# FMC_HPC_TO_LPC_BREAKOUT_ROW_HPC1.net
KiCad netlist of a schematic drawn in Altium Designer
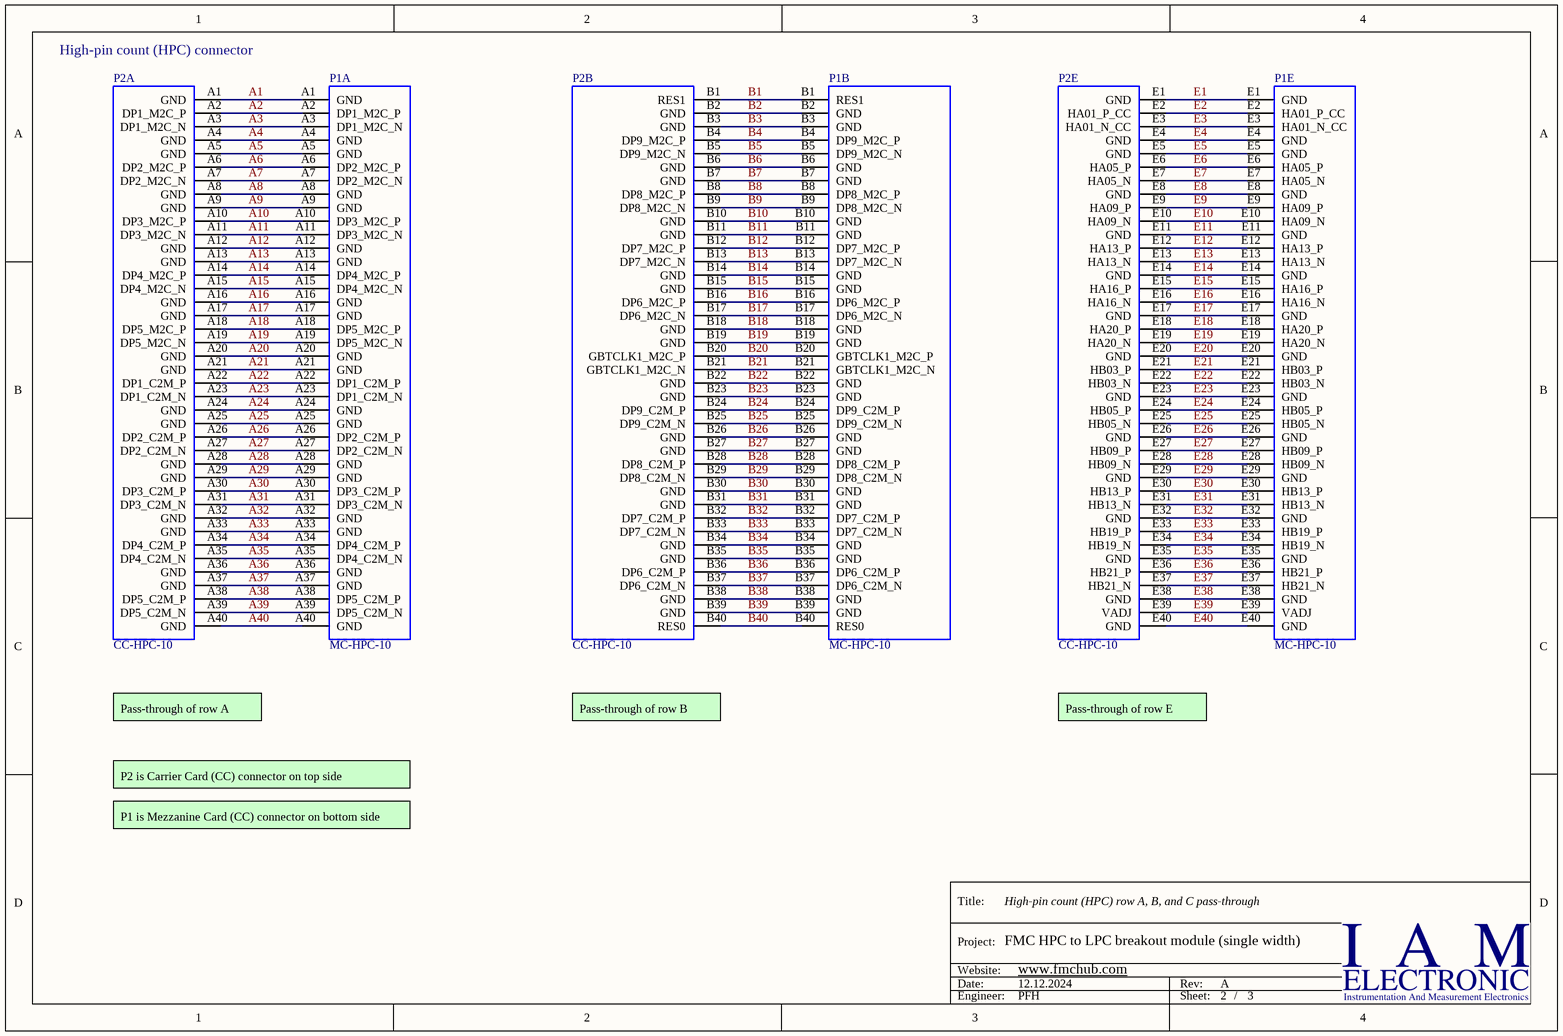
[diagram p0: FMC_HPC_TO_LPC_BREAKOUT_ROW_HPC1.SchDoc]

(export (version "E")
  (design (tool "Eeschema 10.0.6"))
  (components
    (comp (ref "P1")
      (value "MC-HPC-10")
      (footprint "ASP-134488-01")
      (description "MC-HPC-10, FMC High-pin count connector, lead free, 400 I/Os, male, 10 mm mated stack height")
      (fields (field (name "MANUFACTURER") "Samtec") (field (name "PART") "ASP-134488-01"))
      (libsource (lib "VITA_57_FMC") (part "MC-HPC-10"))
    )
    (comp (ref "P2")
      (value "CC-HPC-10")
      (footprint "ASP-134486-01")
      (description "CC-HPC-10, FMC High-pin count connector, lead free, 400 I/Os, female, 10 mm mated stack height")
      (fields (field (name "MANUFACTURER") "Samtec") (field (name "PART") "ASP-134486-01"))
      (libsource (lib "VITA_57_FMC") (part "CC-HPC-10"))
    )
  )
  (nets
    (net (code "1") (name "/A1") (class "Default")
      (node (ref "P1") (pin "A1") (pinfunction "GND_A1") (pintype "passive"))
      (node (ref "P2") (pin "A1") (pinfunction "GND_A1") (pintype "passive"))
    )
    (net (code "2") (name "/A2") (class "Default")
      (node (ref "P1") (pin "A2") (pinfunction "DP1_M2C_P_A2") (pintype "passive"))
      (node (ref "P2") (pin "A2") (pinfunction "DP1_M2C_P_A2") (pintype "passive"))
    )
    (net (code "3") (name "/A3") (class "Default")
      (node (ref "P1") (pin "A3") (pinfunction "DP1_M2C_N_A3") (pintype "passive"))
      (node (ref "P2") (pin "A3") (pinfunction "DP1_M2C_N_A3") (pintype "passive"))
    )
    (net (code "4") (name "/A4") (class "Default")
      (node (ref "P1") (pin "A4") (pinfunction "GND_A4") (pintype "passive"))
      (node (ref "P2") (pin "A4") (pinfunction "GND_A4") (pintype "passive"))
    )
    (net (code "5") (name "/A5") (class "Default")
      (node (ref "P1") (pin "A5") (pinfunction "GND_A5") (pintype "passive"))
      (node (ref "P2") (pin "A5") (pinfunction "GND_A5") (pintype "passive"))
    )
    (net (code "6") (name "/A6") (class "Default")
      (node (ref "P1") (pin "A6") (pinfunction "DP2_M2C_P_A6") (pintype "passive"))
      (node (ref "P2") (pin "A6") (pinfunction "DP2_M2C_P_A6") (pintype "passive"))
    )
    (net (code "7") (name "/A7") (class "Default")
      (node (ref "P1") (pin "A7") (pinfunction "DP2_M2C_N_A7") (pintype "passive"))
      (node (ref "P2") (pin "A7") (pinfunction "DP2_M2C_N_A7") (pintype "passive"))
    )
    (net (code "8") (name "/A8") (class "Default")
      (node (ref "P1") (pin "A8") (pinfunction "GND_A8") (pintype "passive"))
      (node (ref "P2") (pin "A8") (pinfunction "GND_A8") (pintype "passive"))
    )
    (net (code "9") (name "/A9") (class "Default")
      (node (ref "P1") (pin "A9") (pinfunction "GND_A9") (pintype "passive"))
      (node (ref "P2") (pin "A9") (pinfunction "GND_A9") (pintype "passive"))
    )
    (net (code "10") (name "/A10") (class "Default")
      (node (ref "P1") (pin "A10") (pinfunction "DP3_M2C_P_A10") (pintype "passive"))
      (node (ref "P2") (pin "A10") (pinfunction "DP3_M2C_P_A10") (pintype "passive"))
    )
    (net (code "11") (name "/A11") (class "Default")
      (node (ref "P1") (pin "A11") (pinfunction "DP3_M2C_N_A11") (pintype "passive"))
      (node (ref "P2") (pin "A11") (pinfunction "DP3_M2C_N_A11") (pintype "passive"))
    )
    (net (code "12") (name "/A12") (class "Default")
      (node (ref "P1") (pin "A12") (pinfunction "GND_A12") (pintype "passive"))
      (node (ref "P2") (pin "A12") (pinfunction "GND_A12") (pintype "passive"))
    )
    (net (code "13") (name "/A13") (class "Default")
      (node (ref "P1") (pin "A13") (pinfunction "GND_A13") (pintype "passive"))
      (node (ref "P2") (pin "A13") (pinfunction "GND_A13") (pintype "passive"))
    )
    (net (code "14") (name "/A14") (class "Default")
      (node (ref "P1") (pin "A14") (pinfunction "DP4_M2C_P_A14") (pintype "passive"))
      (node (ref "P2") (pin "A14") (pinfunction "DP4_M2C_P_A14") (pintype "passive"))
    )
    (net (code "15") (name "/A15") (class "Default")
      (node (ref "P1") (pin "A15") (pinfunction "DP4_M2C_N_A15") (pintype "passive"))
      (node (ref "P2") (pin "A15") (pinfunction "DP4_M2C_N_A15") (pintype "passive"))
    )
    (net (code "16") (name "/A16") (class "Default")
      (node (ref "P1") (pin "A16") (pinfunction "GND_A16") (pintype "passive"))
      (node (ref "P2") (pin "A16") (pinfunction "GND_A16") (pintype "passive"))
    )
    (net (code "17") (name "/A17") (class "Default")
      (node (ref "P1") (pin "A17") (pinfunction "GND_A17") (pintype "passive"))
      (node (ref "P2") (pin "A17") (pinfunction "GND_A17") (pintype "passive"))
    )
    (net (code "18") (name "/A18") (class "Default")
      (node (ref "P1") (pin "A18") (pinfunction "DP5_M2C_P_A18") (pintype "passive"))
      (node (ref "P2") (pin "A18") (pinfunction "DP5_M2C_P_A18") (pintype "passive"))
    )
    (net (code "19") (name "/A19") (class "Default")
      (node (ref "P1") (pin "A19") (pinfunction "DP5_M2C_N_A19") (pintype "passive"))
      (node (ref "P2") (pin "A19") (pinfunction "DP5_M2C_N_A19") (pintype "passive"))
    )
    (net (code "20") (name "/A20") (class "Default")
      (node (ref "P1") (pin "A20") (pinfunction "GND_A20") (pintype "passive"))
      (node (ref "P2") (pin "A20") (pinfunction "GND_A20") (pintype "passive"))
    )
    (net (code "21") (name "/A21") (class "Default")
      (node (ref "P1") (pin "A21") (pinfunction "GND_A21") (pintype "passive"))
      (node (ref "P2") (pin "A21") (pinfunction "GND_A21") (pintype "passive"))
    )
    (net (code "22") (name "/A22") (class "Default")
      (node (ref "P1") (pin "A22") (pinfunction "DP1_C2M_P_A22") (pintype "passive"))
      (node (ref "P2") (pin "A22") (pinfunction "DP1_C2M_P_A22") (pintype "passive"))
    )
    (net (code "23") (name "/A23") (class "Default")
      (node (ref "P1") (pin "A23") (pinfunction "DP1_C2M_N_A23") (pintype "passive"))
      (node (ref "P2") (pin "A23") (pinfunction "DP1_C2M_N_A23") (pintype "passive"))
    )
    (net (code "24") (name "/A24") (class "Default")
      (node (ref "P1") (pin "A24") (pinfunction "GND_A24") (pintype "passive"))
      (node (ref "P2") (pin "A24") (pinfunction "GND_A24") (pintype "passive"))
    )
    (net (code "25") (name "/A25") (class "Default")
      (node (ref "P1") (pin "A25") (pinfunction "GND_A25") (pintype "passive"))
      (node (ref "P2") (pin "A25") (pinfunction "GND_A25") (pintype "passive"))
    )
    (net (code "26") (name "/A26") (class "Default")
      (node (ref "P1") (pin "A26") (pinfunction "DP2_C2M_P_A26") (pintype "passive"))
      (node (ref "P2") (pin "A26") (pinfunction "DP2_C2M_P_A26") (pintype "passive"))
    )
    (net (code "27") (name "/A27") (class "Default")
      (node (ref "P1") (pin "A27") (pinfunction "DP2_C2M_N_A27") (pintype "passive"))
      (node (ref "P2") (pin "A27") (pinfunction "DP2_C2M_N_A27") (pintype "passive"))
    )
    (net (code "28") (name "/A28") (class "Default")
      (node (ref "P1") (pin "A28") (pinfunction "GND_A28") (pintype "passive"))
      (node (ref "P2") (pin "A28") (pinfunction "GND_A28") (pintype "passive"))
    )
    (net (code "29") (name "/A29") (class "Default")
      (node (ref "P1") (pin "A29") (pinfunction "GND_A29") (pintype "passive"))
      (node (ref "P2") (pin "A29") (pinfunction "GND_A29") (pintype "passive"))
    )
    (net (code "30") (name "/A30") (class "Default")
      (node (ref "P1") (pin "A30") (pinfunction "DP3_C2M_P_A30") (pintype "passive"))
      (node (ref "P2") (pin "A30") (pinfunction "DP3_C2M_P_A30") (pintype "passive"))
    )
    (net (code "31") (name "/A31") (class "Default")
      (node (ref "P1") (pin "A31") (pinfunction "DP3_C2M_N_A31") (pintype "passive"))
      (node (ref "P2") (pin "A31") (pinfunction "DP3_C2M_N_A31") (pintype "passive"))
    )
    (net (code "32") (name "/A32") (class "Default")
      (node (ref "P1") (pin "A32") (pinfunction "GND_A32") (pintype "passive"))
      (node (ref "P2") (pin "A32") (pinfunction "GND_A32") (pintype "passive"))
    )
    (net (code "33") (name "/A33") (class "Default")
      (node (ref "P1") (pin "A33") (pinfunction "GND_A33") (pintype "passive"))
      (node (ref "P2") (pin "A33") (pinfunction "GND_A33") (pintype "passive"))
    )
    (net (code "34") (name "/A34") (class "Default")
      (node (ref "P1") (pin "A34") (pinfunction "DP4_C2M_P_A34") (pintype "passive"))
      (node (ref "P2") (pin "A34") (pinfunction "DP4_C2M_P_A34") (pintype "passive"))
    )
    (net (code "35") (name "/A35") (class "Default")
      (node (ref "P1") (pin "A35") (pinfunction "DP4_C2M_N_A35") (pintype "passive"))
      (node (ref "P2") (pin "A35") (pinfunction "DP4_C2M_N_A35") (pintype "passive"))
    )
    (net (code "36") (name "/A36") (class "Default")
      (node (ref "P1") (pin "A36") (pinfunction "GND_A36") (pintype "passive"))
      (node (ref "P2") (pin "A36") (pinfunction "GND_A36") (pintype "passive"))
    )
    (net (code "37") (name "/A37") (class "Default")
      (node (ref "P1") (pin "A37") (pinfunction "GND_A37") (pintype "passive"))
      (node (ref "P2") (pin "A37") (pinfunction "GND_A37") (pintype "passive"))
    )
    (net (code "38") (name "/A38") (class "Default")
      (node (ref "P1") (pin "A38") (pinfunction "DP5_C2M_P_A38") (pintype "passive"))
      (node (ref "P2") (pin "A38") (pinfunction "DP5_C2M_P_A38") (pintype "passive"))
    )
    (net (code "39") (name "/A39") (class "Default")
      (node (ref "P1") (pin "A39") (pinfunction "DP5_C2M_N_A39") (pintype "passive"))
      (node (ref "P2") (pin "A39") (pinfunction "DP5_C2M_N_A39") (pintype "passive"))
    )
    (net (code "40") (name "/A40") (class "Default")
      (node (ref "P1") (pin "A40") (pinfunction "GND_A40") (pintype "passive"))
      (node (ref "P2") (pin "A40") (pinfunction "GND_A40") (pintype "passive"))
    )
    (net (code "41") (name "/B1") (class "Default")
      (node (ref "P1") (pin "B1") (pinfunction "RES1_B1") (pintype "passive"))
      (node (ref "P2") (pin "B1") (pinfunction "RES1_B1") (pintype "passive"))
    )
    (net (code "42") (name "/B2") (class "Default")
      (node (ref "P1") (pin "B2") (pinfunction "GND_B2") (pintype "passive"))
      (node (ref "P2") (pin "B2") (pinfunction "GND_B2") (pintype "passive"))
    )
    (net (code "43") (name "/B3") (class "Default")
      (node (ref "P1") (pin "B3") (pinfunction "GND_B3") (pintype "passive"))
      (node (ref "P2") (pin "B3") (pinfunction "GND_B3") (pintype "passive"))
    )
    (net (code "44") (name "/B4") (class "Default")
      (node (ref "P1") (pin "B4") (pinfunction "DP9_M2C_P_B4") (pintype "passive"))
      (node (ref "P2") (pin "B4") (pinfunction "DP9_M2C_P_B4") (pintype "passive"))
    )
    (net (code "45") (name "/B5") (class "Default")
      (node (ref "P1") (pin "B5") (pinfunction "DP9_M2C_N_B5") (pintype "passive"))
      (node (ref "P2") (pin "B5") (pinfunction "DP9_M2C_N_B5") (pintype "passive"))
    )
    (net (code "46") (name "/B6") (class "Default")
      (node (ref "P1") (pin "B6") (pinfunction "GND_B6") (pintype "passive"))
      (node (ref "P2") (pin "B6") (pinfunction "GND_B6") (pintype "passive"))
    )
    (net (code "47") (name "/B7") (class "Default")
      (node (ref "P1") (pin "B7") (pinfunction "GND_B7") (pintype "passive"))
      (node (ref "P2") (pin "B7") (pinfunction "GND_B7") (pintype "passive"))
    )
    (net (code "48") (name "/B8") (class "Default")
      (node (ref "P1") (pin "B8") (pinfunction "DP8_M2C_P_B8") (pintype "passive"))
      (node (ref "P2") (pin "B8") (pinfunction "DP8_M2C_P_B8") (pintype "passive"))
    )
    (net (code "49") (name "/B9") (class "Default")
      (node (ref "P1") (pin "B9") (pinfunction "DP8_M2C_N_B9") (pintype "passive"))
      (node (ref "P2") (pin "B9") (pinfunction "DP8_M2C_N_B9") (pintype "passive"))
    )
    (net (code "50") (name "/B10") (class "Default")
      (node (ref "P1") (pin "B10") (pinfunction "GND_B10") (pintype "passive"))
      (node (ref "P2") (pin "B10") (pinfunction "GND_B10") (pintype "passive"))
    )
    (net (code "51") (name "/B11") (class "Default")
      (node (ref "P1") (pin "B11") (pinfunction "GND_B11") (pintype "passive"))
      (node (ref "P2") (pin "B11") (pinfunction "GND_B11") (pintype "passive"))
    )
    (net (code "52") (name "/B12") (class "Default")
      (node (ref "P1") (pin "B12") (pinfunction "DP7_M2C_P_B12") (pintype "passive"))
      (node (ref "P2") (pin "B12") (pinfunction "DP7_M2C_P_B12") (pintype "passive"))
    )
    (net (code "53") (name "/B13") (class "Default")
      (node (ref "P1") (pin "B13") (pinfunction "DP7_M2C_N_B13") (pintype "passive"))
      (node (ref "P2") (pin "B13") (pinfunction "DP7_M2C_N_B13") (pintype "passive"))
    )
    (net (code "54") (name "/B14") (class "Default")
      (node (ref "P1") (pin "B14") (pinfunction "GND_B14") (pintype "passive"))
      (node (ref "P2") (pin "B14") (pinfunction "GND_B14") (pintype "passive"))
    )
    (net (code "55") (name "/B15") (class "Default")
      (node (ref "P1") (pin "B15") (pinfunction "GND_B15") (pintype "passive"))
      (node (ref "P2") (pin "B15") (pinfunction "GND_B15") (pintype "passive"))
    )
    (net (code "56") (name "/B16") (class "Default")
      (node (ref "P1") (pin "B16") (pinfunction "DP6_M2C_P_B16") (pintype "passive"))
      (node (ref "P2") (pin "B16") (pinfunction "DP6_M2C_P_B16") (pintype "passive"))
    )
    (net (code "57") (name "/B17") (class "Default")
      (node (ref "P1") (pin "B17") (pinfunction "DP6_M2C_N_B17") (pintype "passive"))
      (node (ref "P2") (pin "B17") (pinfunction "DP6_M2C_N_B17") (pintype "passive"))
    )
    (net (code "58") (name "/B18") (class "Default")
      (node (ref "P1") (pin "B18") (pinfunction "GND_B18") (pintype "passive"))
      (node (ref "P2") (pin "B18") (pinfunction "GND_B18") (pintype "passive"))
    )
    (net (code "59") (name "/B19") (class "Default")
      (node (ref "P1") (pin "B19") (pinfunction "GND_B19") (pintype "passive"))
      (node (ref "P2") (pin "B19") (pinfunction "GND_B19") (pintype "passive"))
    )
    (net (code "60") (name "/B20") (class "Default")
      (node (ref "P1") (pin "B20") (pinfunction "GBTCLK1_M2C_P_B20") (pintype "passive"))
      (node (ref "P2") (pin "B20") (pinfunction "GBTCLK1_M2C_P_B20") (pintype "passive"))
    )
    (net (code "61") (name "/B21") (class "Default")
      (node (ref "P1") (pin "B21") (pinfunction "GBTCLK1_M2C_N_B21") (pintype "passive"))
      (node (ref "P2") (pin "B21") (pinfunction "GBTCLK1_M2C_N_B21") (pintype "passive"))
    )
    (net (code "62") (name "/B22") (class "Default")
      (node (ref "P1") (pin "B22") (pinfunction "GND_B22") (pintype "passive"))
      (node (ref "P2") (pin "B22") (pinfunction "GND_B22") (pintype "passive"))
    )
    (net (code "63") (name "/B23") (class "Default")
      (node (ref "P1") (pin "B23") (pinfunction "GND_B23") (pintype "passive"))
      (node (ref "P2") (pin "B23") (pinfunction "GND_B23") (pintype "passive"))
    )
    (net (code "64") (name "/B24") (class "Default")
      (node (ref "P1") (pin "B24") (pinfunction "DP9_C2M_P_B24") (pintype "passive"))
      (node (ref "P2") (pin "B24") (pinfunction "DP9_C2M_P_B24") (pintype "passive"))
    )
    (net (code "65") (name "/B25") (class "Default")
      (node (ref "P1") (pin "B25") (pinfunction "DP9_C2M_N_B25") (pintype "passive"))
      (node (ref "P2") (pin "B25") (pinfunction "DP9_C2M_N_B25") (pintype "passive"))
    )
    (net (code "66") (name "/B26") (class "Default")
      (node (ref "P1") (pin "B26") (pinfunction "GND_B26") (pintype "passive"))
      (node (ref "P2") (pin "B26") (pinfunction "GND_B26") (pintype "passive"))
    )
    (net (code "67") (name "/B27") (class "Default")
      (node (ref "P1") (pin "B27") (pinfunction "GND_B27") (pintype "passive"))
      (node (ref "P2") (pin "B27") (pinfunction "GND_B27") (pintype "passive"))
    )
    (net (code "68") (name "/B28") (class "Default")
      (node (ref "P1") (pin "B28") (pinfunction "DP8_C2M_P_B28") (pintype "passive"))
      (node (ref "P2") (pin "B28") (pinfunction "DP8_C2M_P_B28") (pintype "passive"))
    )
    (net (code "69") (name "/B29") (class "Default")
      (node (ref "P1") (pin "B29") (pinfunction "DP8_C2M_N_B29") (pintype "passive"))
      (node (ref "P2") (pin "B29") (pinfunction "DP8_C2M_N_B29") (pintype "passive"))
    )
    (net (code "70") (name "/B30") (class "Default")
      (node (ref "P1") (pin "B30") (pinfunction "GND_B30") (pintype "passive"))
      (node (ref "P2") (pin "B30") (pinfunction "GND_B30") (pintype "passive"))
    )
    (net (code "71") (name "/B31") (class "Default")
      (node (ref "P1") (pin "B31") (pinfunction "GND_B31") (pintype "passive"))
      (node (ref "P2") (pin "B31") (pinfunction "GND_B31") (pintype "passive"))
    )
    (net (code "72") (name "/B32") (class "Default")
      (node (ref "P1") (pin "B32") (pinfunction "DP7_C2M_P_B32") (pintype "passive"))
      (node (ref "P2") (pin "B32") (pinfunction "DP7_C2M_P_B32") (pintype "passive"))
    )
    (net (code "73") (name "/B33") (class "Default")
      (node (ref "P1") (pin "B33") (pinfunction "DP7_C2M_N_B33") (pintype "passive"))
      (node (ref "P2") (pin "B33") (pinfunction "DP7_C2M_N_B33") (pintype "passive"))
    )
    (net (code "74") (name "/B34") (class "Default")
      (node (ref "P1") (pin "B34") (pinfunction "GND_B34") (pintype "passive"))
      (node (ref "P2") (pin "B34") (pinfunction "GND_B34") (pintype "passive"))
    )
    (net (code "75") (name "/B35") (class "Default")
      (node (ref "P1") (pin "B35") (pinfunction "GND_B35") (pintype "passive"))
      (node (ref "P2") (pin "B35") (pinfunction "GND_B35") (pintype "passive"))
    )
    (net (code "76") (name "/B36") (class "Default")
      (node (ref "P1") (pin "B36") (pinfunction "DP6_C2M_P_B36") (pintype "passive"))
      (node (ref "P2") (pin "B36") (pinfunction "DP6_C2M_P_B36") (pintype "passive"))
    )
    (net (code "77") (name "/B37") (class "Default")
      (node (ref "P1") (pin "B37") (pinfunction "DP6_C2M_N_B37") (pintype "passive"))
      (node (ref "P2") (pin "B37") (pinfunction "DP6_C2M_N_B37") (pintype "passive"))
    )
    (net (code "78") (name "/B38") (class "Default")
      (node (ref "P1") (pin "B38") (pinfunction "GND_B38") (pintype "passive"))
      (node (ref "P2") (pin "B38") (pinfunction "GND_B38") (pintype "passive"))
    )
    (net (code "79") (name "/B39") (class "Default")
      (node (ref "P1") (pin "B39") (pinfunction "GND_B39") (pintype "passive"))
      (node (ref "P2") (pin "B39") (pinfunction "GND_B39") (pintype "passive"))
    )
    (net (code "80") (name "/B40") (class "Default")
      (node (ref "P1") (pin "B40") (pinfunction "RES0_B40") (pintype "passive"))
      (node (ref "P2") (pin "B40") (pinfunction "RES0_B40") (pintype "passive"))
    )
    (net (code "81") (name "/E1") (class "Default")
      (node (ref "P1") (pin "E1") (pinfunction "GND_E1") (pintype "passive"))
      (node (ref "P2") (pin "E1") (pinfunction "GND_E1") (pintype "passive"))
    )
    (net (code "82") (name "/E2") (class "Default")
      (node (ref "P1") (pin "E2") (pinfunction "HA01_P_CC_E2") (pintype "passive"))
      (node (ref "P2") (pin "E2") (pinfunction "HA01_P_CC_E2") (pintype "passive"))
    )
    (net (code "83") (name "/E3") (class "Default")
      (node (ref "P1") (pin "E3") (pinfunction "HA01_N_CC_E3") (pintype "passive"))
      (node (ref "P2") (pin "E3") (pinfunction "HA01_N_CC_E3") (pintype "passive"))
    )
    (net (code "84") (name "/E4") (class "Default")
      (node (ref "P1") (pin "E4") (pinfunction "GND_E4") (pintype "passive"))
      (node (ref "P2") (pin "E4") (pinfunction "GND_E4") (pintype "passive"))
    )
    (net (code "85") (name "/E5") (class "Default")
      (node (ref "P1") (pin "E5") (pinfunction "GND_E5") (pintype "passive"))
      (node (ref "P2") (pin "E5") (pinfunction "GND_E5") (pintype "passive"))
    )
    (net (code "86") (name "/E6") (class "Default")
      (node (ref "P1") (pin "E6") (pinfunction "HA05_P_E6") (pintype "passive"))
      (node (ref "P2") (pin "E6") (pinfunction "HA05_P_E6") (pintype "passive"))
    )
    (net (code "87") (name "/E7") (class "Default")
      (node (ref "P1") (pin "E7") (pinfunction "HA05_N_E7") (pintype "passive"))
      (node (ref "P2") (pin "E7") (pinfunction "HA05_N_E7") (pintype "passive"))
    )
    (net (code "88") (name "/E8") (class "Default")
      (node (ref "P1") (pin "E8") (pinfunction "GND_E8") (pintype "passive"))
      (node (ref "P2") (pin "E8") (pinfunction "GND_E8") (pintype "passive"))
    )
    (net (code "89") (name "/E9") (class "Default")
      (node (ref "P1") (pin "E9") (pinfunction "HA09_P_E9") (pintype "passive"))
      (node (ref "P2") (pin "E9") (pinfunction "HA09_P_E9") (pintype "passive"))
    )
    (net (code "90") (name "/E10") (class "Default")
      (node (ref "P1") (pin "E10") (pinfunction "HA09_N_E10") (pintype "passive"))
      (node (ref "P2") (pin "E10") (pinfunction "HA09_N_E10") (pintype "passive"))
    )
    (net (code "91") (name "/E11") (class "Default")
      (node (ref "P1") (pin "E11") (pinfunction "GND_E11") (pintype "passive"))
      (node (ref "P2") (pin "E11") (pinfunction "GND_E11") (pintype "passive"))
    )
    (net (code "92") (name "/E12") (class "Default")
      (node (ref "P1") (pin "E12") (pinfunction "HA13_P_E12") (pintype "passive"))
      (node (ref "P2") (pin "E12") (pinfunction "HA13_P_E12") (pintype "passive"))
    )
    (net (code "93") (name "/E13") (class "Default")
      (node (ref "P1") (pin "E13") (pinfunction "HA13_N_E13") (pintype "passive"))
      (node (ref "P2") (pin "E13") (pinfunction "HA13_N_E13") (pintype "passive"))
    )
    (net (code "94") (name "/E14") (class "Default")
      (node (ref "P1") (pin "E14") (pinfunction "GND_E14") (pintype "passive"))
      (node (ref "P2") (pin "E14") (pinfunction "GND_E14") (pintype "passive"))
    )
    (net (code "95") (name "/E15") (class "Default")
      (node (ref "P1") (pin "E15") (pinfunction "HA16_P_E15") (pintype "passive"))
      (node (ref "P2") (pin "E15") (pinfunction "HA16_P_E15") (pintype "passive"))
    )
    (net (code "96") (name "/E16") (class "Default")
      (node (ref "P1") (pin "E16") (pinfunction "HA16_N_E16") (pintype "passive"))
      (node (ref "P2") (pin "E16") (pinfunction "HA16_N_E16") (pintype "passive"))
    )
    (net (code "97") (name "/E17") (class "Default")
      (node (ref "P1") (pin "E17") (pinfunction "GND_E17") (pintype "passive"))
      (node (ref "P2") (pin "E17") (pinfunction "GND_E17") (pintype "passive"))
    )
    (net (code "98") (name "/E18") (class "Default")
      (node (ref "P1") (pin "E18") (pinfunction "HA20_P_E18") (pintype "passive"))
      (node (ref "P2") (pin "E18") (pinfunction "HA20_P_E18") (pintype "passive"))
    )
    (net (code "99") (name "/E19") (class "Default")
      (node (ref "P1") (pin "E19") (pinfunction "HA20_N_E19") (pintype "passive"))
      (node (ref "P2") (pin "E19") (pinfunction "HA20_N_E19") (pintype "passive"))
    )
    (net (code "100") (name "/E20") (class "Default")
      (node (ref "P1") (pin "E20") (pinfunction "GND_E20") (pintype "passive"))
      (node (ref "P2") (pin "E20") (pinfunction "GND_E20") (pintype "passive"))
    )
    (net (code "101") (name "/E21") (class "Default")
      (node (ref "P1") (pin "E21") (pinfunction "HB03_P_E21") (pintype "passive"))
      (node (ref "P2") (pin "E21") (pinfunction "HB03_P_E21") (pintype "passive"))
    )
    (net (code "102") (name "/E22") (class "Default")
      (node (ref "P1") (pin "E22") (pinfunction "HB03_N_E22") (pintype "passive"))
      (node (ref "P2") (pin "E22") (pinfunction "HB03_N_E22") (pintype "passive"))
    )
    (net (code "103") (name "/E23") (class "Default")
      (node (ref "P1") (pin "E23") (pinfunction "GND_E23") (pintype "passive"))
      (node (ref "P2") (pin "E23") (pinfunction "GND_E23") (pintype "passive"))
    )
    (net (code "104") (name "/E24") (class "Default")
      (node (ref "P1") (pin "E24") (pinfunction "HB05_P_E24") (pintype "passive"))
      (node (ref "P2") (pin "E24") (pinfunction "HB05_P_E24") (pintype "passive"))
    )
    (net (code "105") (name "/E25") (class "Default")
      (node (ref "P1") (pin "E25") (pinfunction "HB05_N_E25") (pintype "passive"))
      (node (ref "P2") (pin "E25") (pinfunction "HB05_N_E25") (pintype "passive"))
    )
    (net (code "106") (name "/E26") (class "Default")
      (node (ref "P1") (pin "E26") (pinfunction "GND_E26") (pintype "passive"))
      (node (ref "P2") (pin "E26") (pinfunction "GND_E26") (pintype "passive"))
    )
    (net (code "107") (name "/E27") (class "Default")
      (node (ref "P1") (pin "E27") (pinfunction "HB09_P_E27") (pintype "passive"))
      (node (ref "P2") (pin "E27") (pinfunction "HB09_P_E27") (pintype "passive"))
    )
    (net (code "108") (name "/E28") (class "Default")
      (node (ref "P1") (pin "E28") (pinfunction "HB09_N_E28") (pintype "passive"))
      (node (ref "P2") (pin "E28") (pinfunction "HB09_N_E28") (pintype "passive"))
    )
    (net (code "109") (name "/E29") (class "Default")
      (node (ref "P1") (pin "E29") (pinfunction "GND_E29") (pintype "passive"))
      (node (ref "P2") (pin "E29") (pinfunction "GND_E29") (pintype "passive"))
    )
    (net (code "110") (name "/E30") (class "Default")
      (node (ref "P1") (pin "E30") (pinfunction "HB13_P_E30") (pintype "passive"))
      (node (ref "P2") (pin "E30") (pinfunction "HB13_P_E30") (pintype "passive"))
    )
    (net (code "111") (name "/E31") (class "Default")
      (node (ref "P1") (pin "E31") (pinfunction "HB13_N_E31") (pintype "passive"))
      (node (ref "P2") (pin "E31") (pinfunction "HB13_N_E31") (pintype "passive"))
    )
    (net (code "112") (name "/E32") (class "Default")
      (node (ref "P1") (pin "E32") (pinfunction "GND_E32") (pintype "passive"))
      (node (ref "P2") (pin "E32") (pinfunction "GND_E32") (pintype "passive"))
    )
    (net (code "113") (name "/E33") (class "Default")
      (node (ref "P1") (pin "E33") (pinfunction "HB19_P_E33") (pintype "passive"))
      (node (ref "P2") (pin "E33") (pinfunction "HB19_P_E33") (pintype "passive"))
    )
    (net (code "114") (name "/E34") (class "Default")
      (node (ref "P1") (pin "E34") (pinfunction "HB19_N_E34") (pintype "passive"))
      (node (ref "P2") (pin "E34") (pinfunction "HB19_N_E34") (pintype "passive"))
    )
    (net (code "115") (name "/E35") (class "Default")
      (node (ref "P1") (pin "E35") (pinfunction "GND_E35") (pintype "passive"))
      (node (ref "P2") (pin "E35") (pinfunction "GND_E35") (pintype "passive"))
    )
    (net (code "116") (name "/E36") (class "Default")
      (node (ref "P1") (pin "E36") (pinfunction "HB21_P_E36") (pintype "passive"))
      (node (ref "P2") (pin "E36") (pinfunction "HB21_P_E36") (pintype "passive"))
    )
    (net (code "117") (name "/E37") (class "Default")
      (node (ref "P1") (pin "E37") (pinfunction "HB21_N_E37") (pintype "passive"))
      (node (ref "P2") (pin "E37") (pinfunction "HB21_N_E37") (pintype "passive"))
    )
    (net (code "118") (name "/E38") (class "Default")
      (node (ref "P1") (pin "E38") (pinfunction "GND_E38") (pintype "passive"))
      (node (ref "P2") (pin "E38") (pinfunction "GND_E38") (pintype "passive"))
    )
    (net (code "119") (name "/E39") (class "Default")
      (node (ref "P1") (pin "E39") (pinfunction "VADJ_E39") (pintype "passive"))
      (node (ref "P2") (pin "E39") (pinfunction "VADJ_E39") (pintype "passive"))
    )
    (net (code "120") (name "/E40") (class "Default")
      (node (ref "P1") (pin "E40") (pinfunction "GND_E40") (pintype "passive"))
      (node (ref "P2") (pin "E40") (pinfunction "GND_E40") (pintype "passive"))
    )
  )
)
